# 9DTact_LED_ProEAD.net
KiCad netlist of a schematic drawn in EasyEDA Pro
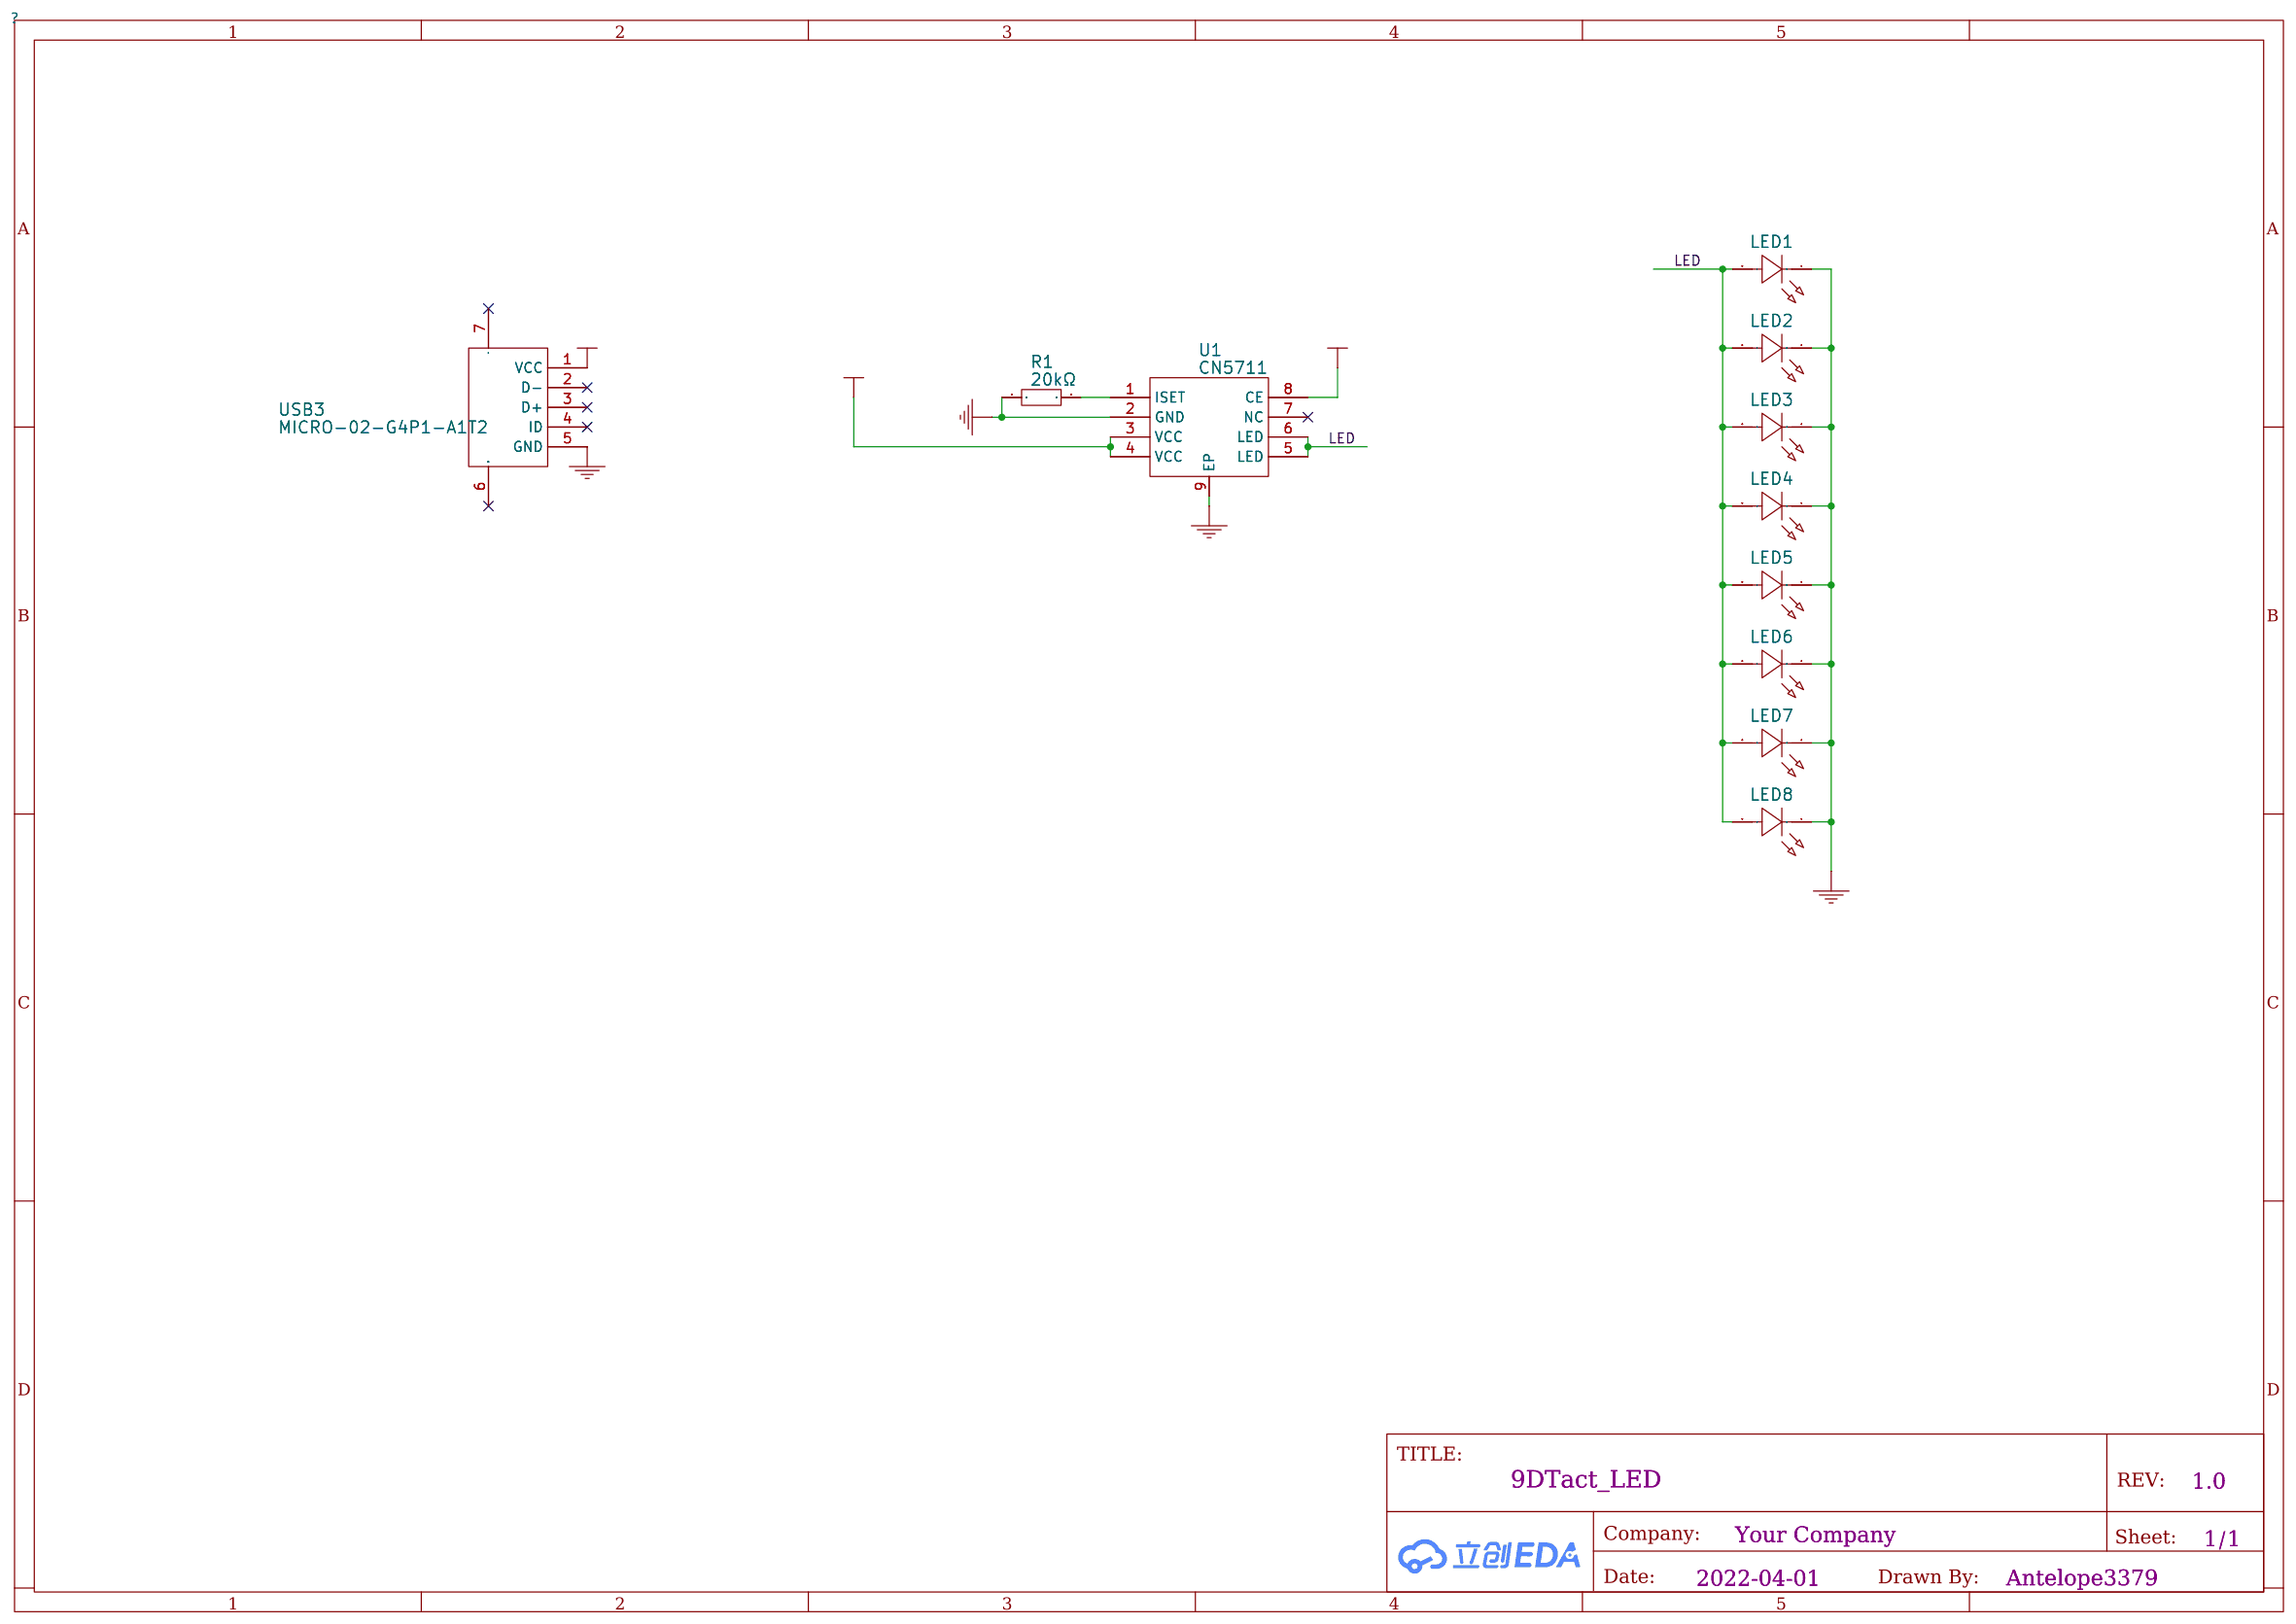
[diagram p0: schematic sheet]

(export (version "E")
  (design (tool "Eeschema 10.0.6"))
  (components
    (comp (ref "LED1")
      (value "BZ-S2835BW9C1-02-3V-UV")
      (footprint "easyedapro:LED-SMD_L3.5-W2.8-FD-2835_WHITE")
      (fields (field (name "Manufacturer") "baizou(百洲）"))
      (libsource (lib "easyedapro") (part "BZ-S2835BW9C1-02-3V-UV"))
    )
    (comp (ref "LED2")
      (value "BZ-S2835BW9C1-02-3V-UV")
      (footprint "easyedapro:LED-SMD_L3.5-W2.8-FD-2835_WHITE")
      (fields (field (name "Manufacturer") "baizou(百洲）"))
      (libsource (lib "easyedapro") (part "BZ-S2835BW9C1-02-3V-UV"))
    )
    (comp (ref "LED3")
      (value "BZ-S2835BW9C1-02-3V-UV")
      (footprint "easyedapro:LED-SMD_L3.5-W2.8-FD-2835_WHITE")
      (fields (field (name "Manufacturer") "baizou(百洲）"))
      (libsource (lib "easyedapro") (part "BZ-S2835BW9C1-02-3V-UV"))
    )
    (comp (ref "LED4")
      (value "BZ-S2835BW9C1-02-3V-UV")
      (footprint "easyedapro:LED-SMD_L3.5-W2.8-FD-2835_WHITE")
      (fields (field (name "Manufacturer") "baizou(百洲）"))
      (libsource (lib "easyedapro") (part "BZ-S2835BW9C1-02-3V-UV"))
    )
    (comp (ref "LED5")
      (value "BZ-S2835BW9C1-02-3V-UV")
      (footprint "easyedapro:LED-SMD_L3.5-W2.8-FD-2835_WHITE")
      (fields (field (name "Manufacturer") "baizou(百洲）"))
      (libsource (lib "easyedapro") (part "BZ-S2835BW9C1-02-3V-UV"))
    )
    (comp (ref "LED6")
      (value "BZ-S2835BW9C1-02-3V-UV")
      (footprint "easyedapro:LED-SMD_L3.5-W2.8-FD-2835_WHITE")
      (fields (field (name "Manufacturer") "baizou(百洲）"))
      (libsource (lib "easyedapro") (part "BZ-S2835BW9C1-02-3V-UV"))
    )
    (comp (ref "LED7")
      (value "BZ-S2835BW9C1-02-3V-UV")
      (footprint "easyedapro:LED-SMD_L3.5-W2.8-FD-2835_WHITE")
      (fields (field (name "Manufacturer") "baizou(百洲）"))
      (libsource (lib "easyedapro") (part "BZ-S2835BW9C1-02-3V-UV"))
    )
    (comp (ref "LED8")
      (value "BZ-S2835BW9C1-02-3V-UV")
      (footprint "easyedapro:LED-SMD_L3.5-W2.8-FD-2835_WHITE")
      (fields (field (name "Manufacturer") "baizou(百洲）"))
      (libsource (lib "easyedapro") (part "BZ-S2835BW9C1-02-3V-UV"))
    )
    (comp (ref "R1")
      (value "20kΩ")
      (footprint "easyedapro:R0805")
      (fields (field (name "Manufacturer Part") "RT0805CRE0720KL") (field (name "Manufacturer") "YAGEO(国巨)"))
      (libsource (lib "easyedapro") (part "3.75kΩ"))
    )
    (comp (ref "U1")
      (value "CN5711")
      (footprint "easyedapro:SOIC-8_L5.0-W4.0-P1.27-LS6.0-BL-EP2.0")
      (fields (field (name "Manufacturer") "CONSONANCE(上海如韵)"))
      (libsource (lib "easyedapro") (part "CN5711"))
    )
    (comp (ref "USB3")
      (value "MICRO-02-G4P1-A1T2")
      (footprint "easyedapro:MICRO-USB-SMD_MICRO-02-GXPX-A1T2")
      (fields (field (name "Manufacturer") "Yuandi(台湾元迪)"))
      (libsource (lib "easyedapro") (part "MICRO-02-G4P1-A1T2"))
    )
  )
  (nets
    (net (code "1") (name "/LED") (class "Default")
      (node (ref "LED1") (pin "2") (pinfunction "A_2") (pintype "input"))
      (node (ref "LED2") (pin "2") (pinfunction "A_2") (pintype "input"))
      (node (ref "LED3") (pin "2") (pinfunction "A_2") (pintype "input"))
      (node (ref "LED4") (pin "2") (pinfunction "A_2") (pintype "input"))
      (node (ref "LED5") (pin "2") (pinfunction "A_2") (pintype "input"))
      (node (ref "LED6") (pin "2") (pinfunction "A_2") (pintype "input"))
      (node (ref "LED7") (pin "2") (pinfunction "A_2") (pintype "input"))
      (node (ref "LED8") (pin "2") (pinfunction "A_2") (pintype "input"))
      (node (ref "U1") (pin "5") (pinfunction "LED_5") (pintype "input"))
      (node (ref "U1") (pin "6") (pinfunction "LED_6") (pintype "input"))
    )
    (net (code "2") (name "GND") (class "Default")
      (node (ref "LED1") (pin "1") (pinfunction "K_1") (pintype "input"))
      (node (ref "LED2") (pin "1") (pinfunction "K_1") (pintype "input"))
      (node (ref "LED3") (pin "1") (pinfunction "K_1") (pintype "input"))
      (node (ref "LED4") (pin "1") (pinfunction "K_1") (pintype "input"))
      (node (ref "LED5") (pin "1") (pinfunction "K_1") (pintype "input"))
      (node (ref "LED6") (pin "1") (pinfunction "K_1") (pintype "input"))
      (node (ref "LED7") (pin "1") (pinfunction "K_1") (pintype "input"))
      (node (ref "LED8") (pin "1") (pinfunction "K_1") (pintype "input"))
      (node (ref "R1") (pin "1") (pinfunction "1_1") (pintype "input"))
      (node (ref "U1") (pin "2") (pinfunction "GND_2") (pintype "input"))
      (node (ref "U1") (pin "9") (pinfunction "EP_9") (pintype "input"))
      (node (ref "USB3") (pin "5") (pinfunction "GND_5") (pintype "input"))
    )
    (net (code "3") (name "Net-(U1-ISET)") (class "Default")
      (node (ref "R1") (pin "2") (pinfunction "2_2") (pintype "input"))
      (node (ref "U1") (pin "1") (pinfunction "ISET_1") (pintype "input"))
    )
    (net (code "4") (name "VCC") (class "Default")
      (node (ref "U1") (pin "3") (pinfunction "VCC_3") (pintype "input"))
      (node (ref "U1") (pin "4") (pinfunction "VCC_4") (pintype "input"))
      (node (ref "U1") (pin "8") (pinfunction "CE_8") (pintype "input"))
      (node (ref "USB3") (pin "1") (pinfunction "VCC_1") (pintype "input"))
    )
    (net (code "5") (name "unconnected-(U1-NC-Pad7)") (class "Default")
      (node (ref "U1") (pin "7") (pinfunction "NC_7") (pintype "input+no_connect"))
    )
    (net (code "6") (name "unconnected-(USB3-D+-Pad3)") (class "Default")
      (node (ref "USB3") (pin "3") (pinfunction "D+_3") (pintype "input+no_connect"))
    )
    (net (code "7") (name "unconnected-(USB3-D--Pad2)") (class "Default")
      (node (ref "USB3") (pin "2") (pinfunction "D-_2") (pintype "input+no_connect"))
    )
    (net (code "8") (name "unconnected-(USB3-ID-Pad4)") (class "Default")
      (node (ref "USB3") (pin "4") (pinfunction "ID_4") (pintype "input+no_connect"))
    )
    (net (code "9") (name "unconnected-(USB3-Pad6)") (class "Default")
      (node (ref "USB3") (pin "6") (pinfunction "6_6") (pintype "input+no_connect"))
    )
    (net (code "10") (name "unconnected-(USB3-Pad7)") (class "Default")
      (node (ref "USB3") (pin "7") (pinfunction "7_7") (pintype "input+no_connect"))
    )
  )
)
